# MPU-9250.net
KiCad netlist of a schematic drawn in EAGLE
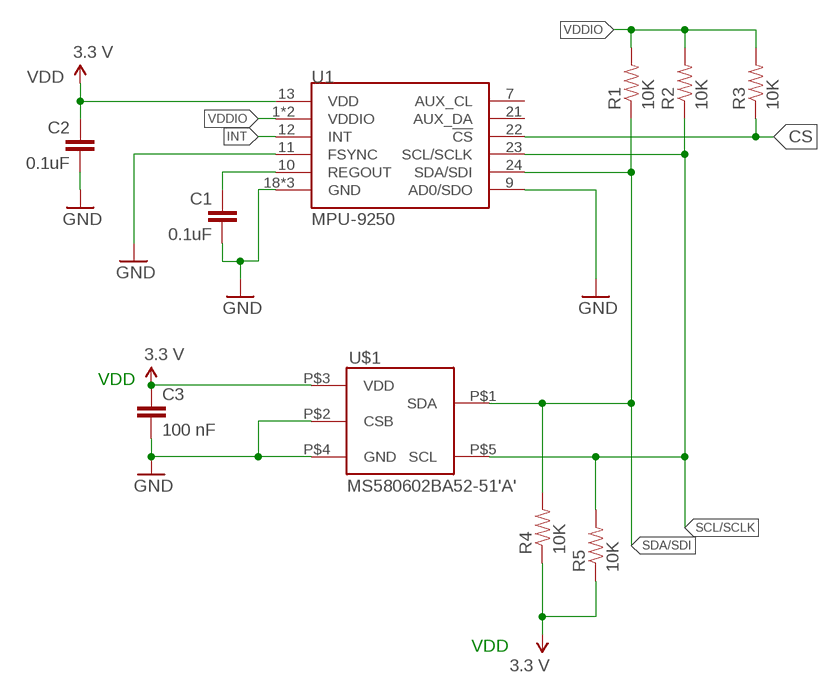
[diagram p0: schematic, sheet 1]

(export (version "E")
  (design (tool "Eeschema 10.0.6"))
  (components
    (comp (ref "C1")
      (value "0.1uF")
      (footprint "eagle-import:0603-CAP")
      (libsource (lib "eagle-import") (part "0.1UF-25V(+80/-20%)(0603)"))
    )
    (comp (ref "C2")
      (value "0.1uF")
      (footprint "eagle-import:0603-CAP")
      (libsource (lib "eagle-import") (part "0.1UF-25V(+80/-20%)(0603)"))
    )
    (comp (ref "C3")
      (value "100 nF")
      (footprint "eagle-import:C4564")
      (libsource (lib "eagle-import") (part "CC4564"))
    )
    (comp (ref "R1")
      (value "10K")
      (footprint "eagle-import:0603-RES")
      (libsource (lib "eagle-import") (part "10KOHM-1/10W-1%(0603)0603"))
    )
    (comp (ref "R2")
      (value "10K")
      (footprint "eagle-import:0603-RES")
      (libsource (lib "eagle-import") (part "10KOHM-1/10W-1%(0603)0603"))
    )
    (comp (ref "R3")
      (value "10K")
      (footprint "eagle-import:0603-RES")
      (libsource (lib "eagle-import") (part "10KOHM-1/10W-1%(0603)0603"))
    )
    (comp (ref "R4")
      (value "10K")
      (footprint "eagle-import:0603-RES")
      (libsource (lib "eagle-import") (part "10KOHM-1/10W-1%(0603)0603"))
    )
    (comp (ref "R5")
      (value "10K")
      (footprint "eagle-import:0603-RES")
      (libsource (lib "eagle-import") (part "10KOHM-1/10W-1%(0603)0603"))
    )
    (comp (ref "U$1")
      (value "MS580602BA52-51'A'")
      (footprint "eagle-import:MS5806-02BA")
      (libsource (lib "eagle-import") (part "MS580602BA52-51'A'"))
    )
    (comp (ref "U1")
      (value "MPU-9250")
      (footprint "eagle-import:QFN24_PAD")
      (libsource (lib "eagle-import") (part "MPU-9250"))
    )
  )
  (nets
    (net (code "1") (name "3.3 V") (class "Default")
      (node (ref "C2") (pin "1") (pinfunction "1_1") (pintype "passive"))
      (node (ref "C3") (pin "1") (pinfunction "1_1") (pintype "passive"))
      (node (ref "R4") (pin "1") (pinfunction "1_1") (pintype "passive"))
      (node (ref "R5") (pin "1") (pinfunction "1_1") (pintype "passive"))
      (node (ref "U$1") (pin "P$3") (pinfunction "VDD_P$3") (pintype "bidirectional"))
      (node (ref "U1") (pin "13") (pinfunction "VDD_13") (pintype "bidirectional"))
    )
    (net (code "2") (name "CS") (class "Default")
      (node (ref "R3") (pin "1") (pinfunction "1_1") (pintype "passive"))
      (node (ref "U1") (pin "22") (pinfunction "~{CS}_22") (pintype "bidirectional"))
    )
    (net (code "3") (name "GND") (class "Default")
      (node (ref "C1") (pin "2") (pinfunction "2_2") (pintype "passive"))
      (node (ref "C2") (pin "2") (pinfunction "2_2") (pintype "passive"))
      (node (ref "C3") (pin "2") (pinfunction "2_2") (pintype "passive"))
      (node (ref "U$1") (pin "P$2") (pinfunction "CSB_P$2") (pintype "bidirectional"))
      (node (ref "U$1") (pin "P$4") (pinfunction "GND_P$4") (pintype "bidirectional"))
      (node (ref "U1") (pin "11") (pinfunction "FSYNC_11") (pintype "bidirectional"))
      (node (ref "U1") (pin "18") (pinfunction "GND_18") (pintype "bidirectional"))
      (node (ref "U1") (pin "20") (pinfunction "GND_20") (pintype "bidirectional"))
      (node (ref "U1") (pin "9") (pinfunction "AD0/SDO_9") (pintype "bidirectional"))
      (node (ref "U1") (pin "CENTER") (pinfunction "GND_CENTER") (pintype "bidirectional"))
    )
    (net (code "4") (name "INT") (class "Default")
      (node (ref "U1") (pin "12") (pinfunction "INT_12") (pintype "bidirectional"))
    )
    (net (code "5") (name "Net-(U1-REGOUT)") (class "Default")
      (node (ref "C1") (pin "1") (pinfunction "1_1") (pintype "passive"))
      (node (ref "U1") (pin "10") (pinfunction "REGOUT_10") (pintype "bidirectional"))
    )
    (net (code "6") (name "SCL{slash}SCLK") (class "Default")
      (node (ref "R2") (pin "1") (pinfunction "1_1") (pintype "passive"))
      (node (ref "R5") (pin "2") (pinfunction "2_2") (pintype "passive"))
      (node (ref "U$1") (pin "P$5") (pinfunction "SCL_P$5") (pintype "bidirectional"))
      (node (ref "U1") (pin "23") (pinfunction "SCL/SCLK_23") (pintype "bidirectional"))
    )
    (net (code "7") (name "SDA{slash}SDI") (class "Default")
      (node (ref "R1") (pin "1") (pinfunction "1_1") (pintype "passive"))
      (node (ref "R4") (pin "2") (pinfunction "2_2") (pintype "passive"))
      (node (ref "U$1") (pin "P$1") (pinfunction "SDA_P$1") (pintype "bidirectional"))
      (node (ref "U1") (pin "24") (pinfunction "SDA/SDI_24") (pintype "bidirectional"))
    )
    (net (code "8") (name "VDDIO") (class "Default")
      (node (ref "R1") (pin "2") (pinfunction "2_2") (pintype "passive"))
      (node (ref "R2") (pin "2") (pinfunction "2_2") (pintype "passive"))
      (node (ref "R3") (pin "2") (pinfunction "2_2") (pintype "passive"))
      (node (ref "U1") (pin "1") (pinfunction "VDDIO_1") (pintype "bidirectional"))
      (node (ref "U1") (pin "8") (pinfunction "VDDIO_8") (pintype "bidirectional"))
    )
    (net (code "9") (name "unconnected-(U1-AUX_CL-Pad7)") (class "Default")
      (node (ref "U1") (pin "7") (pinfunction "AUX_CL_7") (pintype "bidirectional"))
    )
    (net (code "10") (name "unconnected-(U1-AUX_DA-Pad21)") (class "Default")
      (node (ref "U1") (pin "21") (pinfunction "AUX_DA_21") (pintype "bidirectional"))
    )
  )
)
